# SparkX_EZ_LiPo_Power.net
KiCad netlist of a schematic drawn in EAGLE
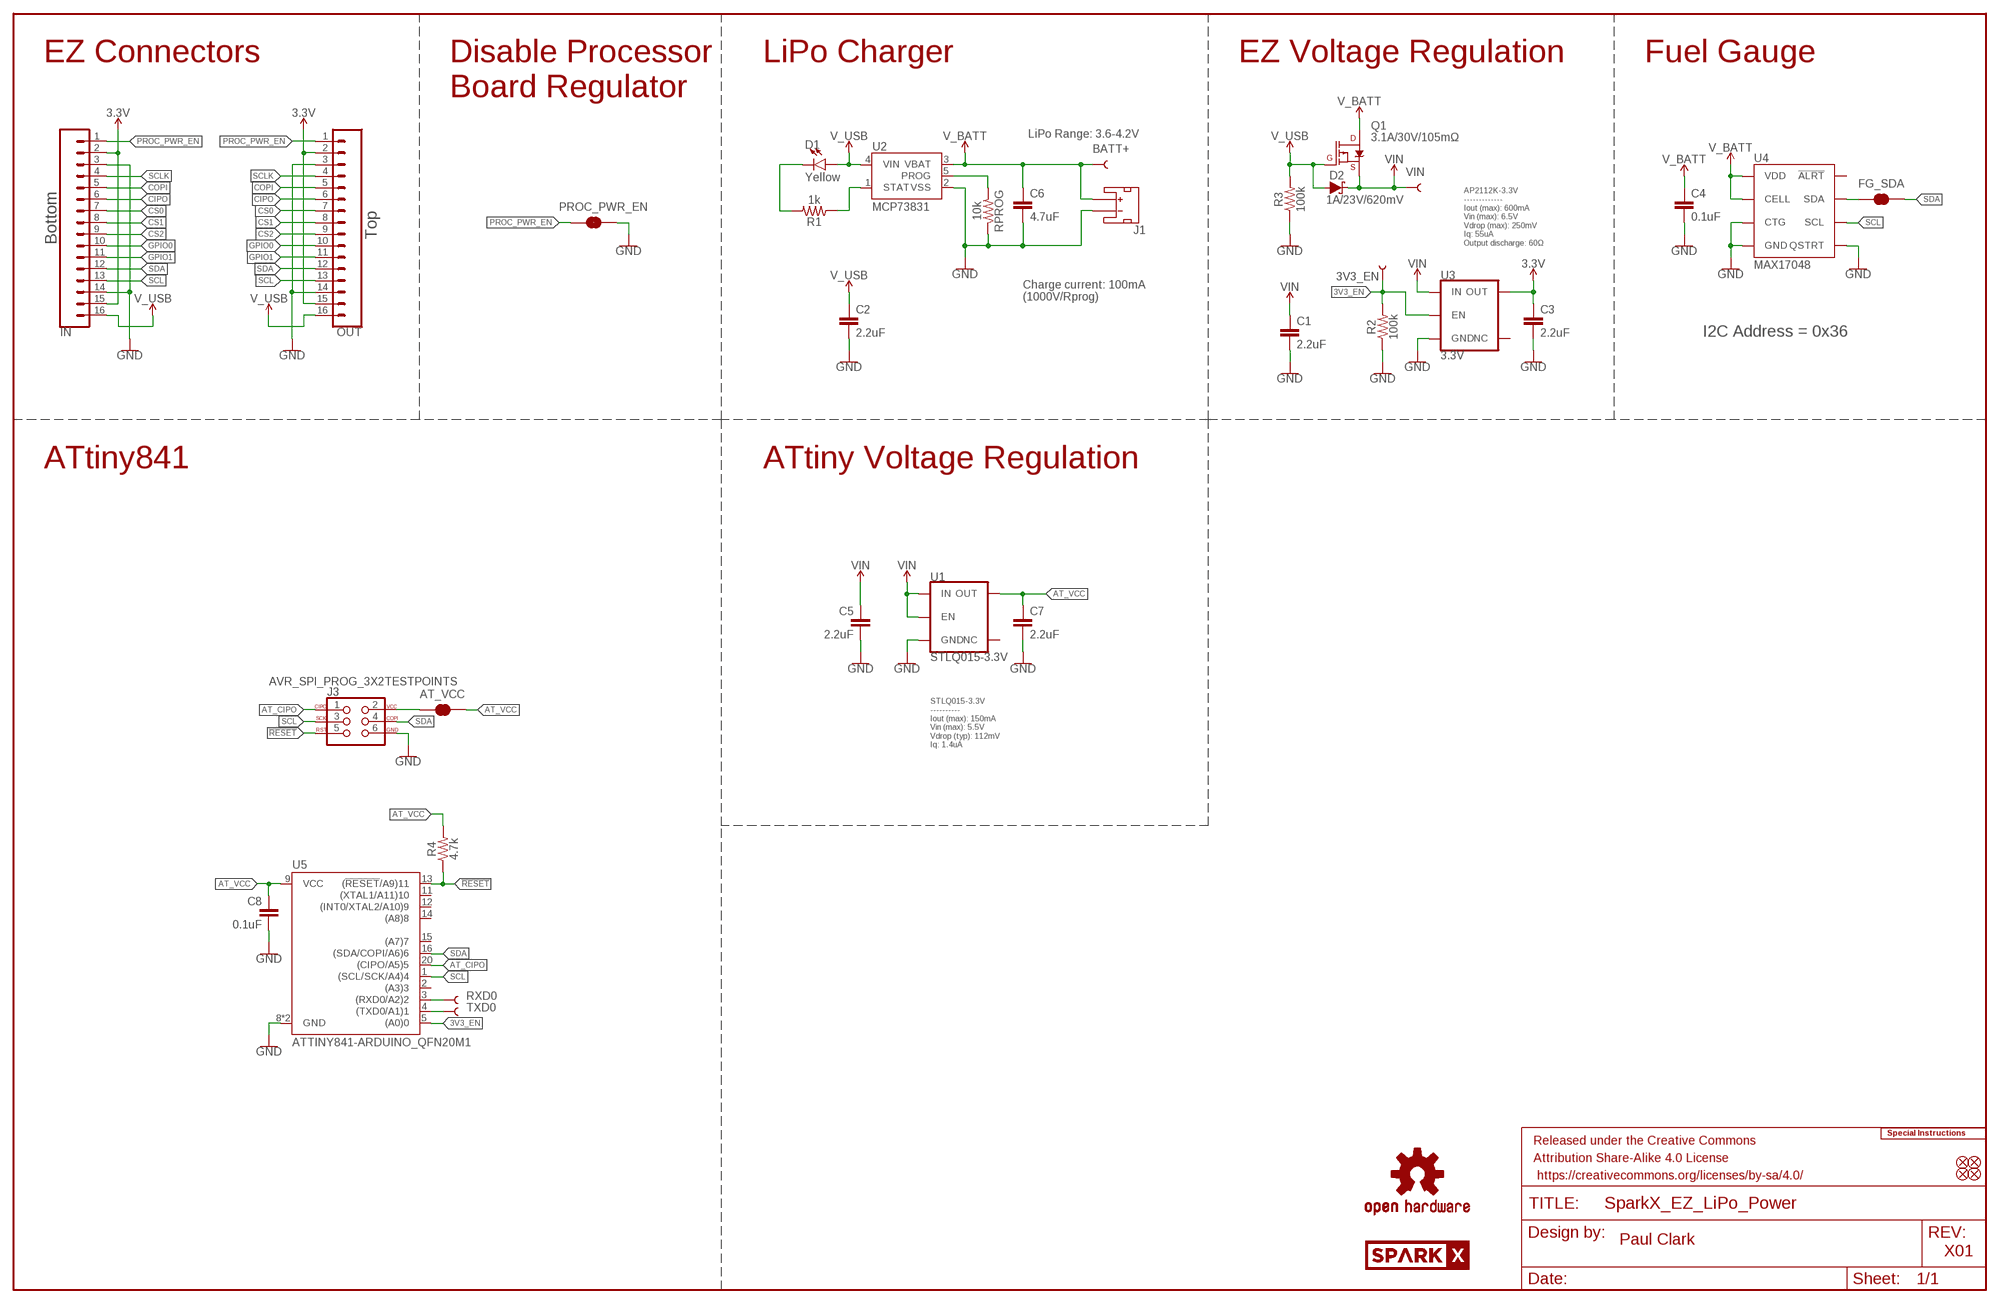
[diagram p0: schematic, sheet 1]

(export (version "E")
  (design (tool "Eeschema 10.0.6"))
  (components
    (comp (ref "3V3_EN")
      (value "TEST-POINT3X4")
      (footprint "eagle-import:PAD.03X.04")
      (libsource (lib "eagle-import") (part "TEST-POINT3X4"))
    )
    (comp (ref "AT_VCC")
      (value "JUMPER-SMT_2_NC_TRACE_SILK")
      (footprint "eagle-import:SMT-JUMPER_2_NC_TRACE_SILK")
      (libsource (lib "eagle-import") (part "JUMPER-SMT_2_NC_TRACE_SILK"))
    )
    (comp (ref "BATT+")
      (value "TEST-POINT3X4")
      (footprint "eagle-import:PAD.03X.04")
      (libsource (lib "eagle-import") (part "TEST-POINT3X4"))
    )
    (comp (ref "C1")
      (value "2.2uF")
      (footprint "eagle-import:0402-TIGHT")
      (libsource (lib "eagle-import") (part "2.2UF-0402_TIGHT-10V-10%-X5R"))
    )
    (comp (ref "C2")
      (value "2.2uF")
      (footprint "eagle-import:0402-TIGHT")
      (libsource (lib "eagle-import") (part "2.2UF-0402_TIGHT-10V-10%-X5R"))
    )
    (comp (ref "C3")
      (value "2.2uF")
      (footprint "eagle-import:0402-TIGHT")
      (libsource (lib "eagle-import") (part "2.2UF-0402_TIGHT-10V-10%-X5R"))
    )
    (comp (ref "C4")
      (value "0.1uF")
      (footprint "eagle-import:0402-TIGHT")
      (libsource (lib "eagle-import") (part "0.1UF-0402T-6.3V-10%-X7R"))
    )
    (comp (ref "C5")
      (value "2.2uF")
      (footprint "eagle-import:0402-TIGHT")
      (libsource (lib "eagle-import") (part "2.2UF-0402_TIGHT-10V-10%-X5R"))
    )
    (comp (ref "C6")
      (value "4.7uF")
      (footprint "eagle-import:0402-TIGHT")
      (libsource (lib "eagle-import") (part "4.7UF-0402_TIGHT-6.3V-20%-X5R"))
    )
    (comp (ref "C7")
      (value "2.2uF")
      (footprint "eagle-import:0402-TIGHT")
      (libsource (lib "eagle-import") (part "2.2UF-0402_TIGHT-10V-10%-X5R"))
    )
    (comp (ref "C8")
      (value "0.1uF")
      (footprint "eagle-import:0402-TIGHT")
      (libsource (lib "eagle-import") (part "0.1UF-0402T-6.3V-10%-X7R"))
    )
    (comp (ref "D1")
      (value "Yellow")
      (footprint "eagle-import:LED-0603")
      (libsource (lib "eagle-import") (part "LED-YELLOW0603"))
    )
    (comp (ref "D2")
      (value "1A/23V/620mV")
      (footprint "eagle-import:SOD-323")
      (libsource (lib "eagle-import") (part "DIODE-SCHOTTKY-BAT20J"))
    )
    (comp (ref "FD1")
      (value "FIDUCIALUFIDUCIAL")
      (footprint "eagle-import:FIDUCIAL-MICRO")
      (libsource (lib "eagle-import") (part "FIDUCIALUFIDUCIAL"))
    )
    (comp (ref "FD2")
      (value "FIDUCIALUFIDUCIAL")
      (footprint "eagle-import:FIDUCIAL-MICRO")
      (libsource (lib "eagle-import") (part "FIDUCIALUFIDUCIAL"))
    )
    (comp (ref "FD3")
      (value "FIDUCIALUFIDUCIAL")
      (footprint "eagle-import:FIDUCIAL-MICRO")
      (libsource (lib "eagle-import") (part "FIDUCIALUFIDUCIAL"))
    )
    (comp (ref "FD4")
      (value "FIDUCIALUFIDUCIAL")
      (footprint "eagle-import:FIDUCIAL-MICRO")
      (libsource (lib "eagle-import") (part "FIDUCIALUFIDUCIAL"))
    )
    (comp (ref "FG_SDA")
      (value "JUMPER-SMT_2_NC_TRACE_SILK")
      (footprint "eagle-import:SMT-JUMPER_2_NC_TRACE_SILK")
      (libsource (lib "eagle-import") (part "JUMPER-SMT_2_NC_TRACE_SILK"))
    )
    (comp (ref "FRAME1")
      (value "FRAME-LEDGER")
      (footprint "eagle-import:CREATIVE_COMMONS")
      (libsource (lib "eagle-import") (part "FRAME-LEDGER"))
    )
    (comp (ref "IN")
      (value "CONN_16FPC_16_0.5MM")
      (footprint "eagle-import:FPC_16_0.5MM")
      (libsource (lib "eagle-import") (part "CONN_16FPC_16_0.5MM"))
    )
    (comp (ref "J1")
      (value "JST_2MM_MALE")
      (footprint "eagle-import:JST-2-SMD")
      (libsource (lib "eagle-import") (part "JST_2MM_MALE"))
    )
    (comp (ref "J3")
      (value "AVR_SPI_PROG_3X2TESTPOINTS")
      (footprint "eagle-import:2X3_TEST_POINTS")
      (libsource (lib "eagle-import") (part "AVR_SPI_PROG_3X2TESTPOINTS"))
    )
    (comp (ref "LOGO1")
      (value "SPECIAL_INSTRUCTIONS-ORDERING")
      (footprint "eagle-import:ORDERING_INSTRUCTIONS")
      (libsource (lib "eagle-import") (part "SPECIAL_INSTRUCTIONS-ORDERING"))
    )
    (comp (ref "LOGO2")
      (value "OSHW-LOGOMINI")
      (footprint "eagle-import:OSHW-LOGO-MINI")
      (libsource (lib "eagle-import") (part "OSHW-LOGOMINI"))
    )
    (comp (ref "LOGO3")
      (value "OSHW-LOGOMINI")
      (footprint "eagle-import:OSHW-LOGO-MINI")
      (libsource (lib "eagle-import") (part "OSHW-LOGOMINI"))
    )
    (comp (ref "OUT")
      (value "CONN_16FPC_16_0.5MM")
      (footprint "eagle-import:FPC_16_0.5MM")
      (libsource (lib "eagle-import") (part "CONN_16FPC_16_0.5MM"))
    )
    (comp (ref "PROC_PWR_EN")
      (value "JUMPER-SMT_2_NC_TRACE_SILK")
      (footprint "eagle-import:SMT-JUMPER_2_NC_TRACE_SILK")
      (libsource (lib "eagle-import") (part "JUMPER-SMT_2_NC_TRACE_SILK"))
    )
    (comp (ref "Q1")
      (value "3.1A/30V/105mΩ")
      (footprint "eagle-import:SOT23-3")
      (libsource (lib "eagle-import") (part "MOSFET_PCH-DMG2307L"))
    )
    (comp (ref "R1")
      (value "1k")
      (footprint "eagle-import:0402-TIGHT")
      (libsource (lib "eagle-import") (part "1KOHM-0402T-1/16W-1%"))
    )
    (comp (ref "R2")
      (value "100k")
      (footprint "eagle-import:0402-TIGHT")
      (libsource (lib "eagle-import") (part "100KOHM-0402T-1/16W-1%"))
    )
    (comp (ref "R3")
      (value "100k")
      (footprint "eagle-import:0402-TIGHT")
      (libsource (lib "eagle-import") (part "100KOHM-0402T-1/16W-1%"))
    )
    (comp (ref "R4")
      (value "4.7k")
      (footprint "eagle-import:0402-TIGHT")
      (libsource (lib "eagle-import") (part "4.7KOHM-0402T-1/16W-1%"))
    )
    (comp (ref "RPROG")
      (value "10k")
      (footprint "eagle-import:0402-TIGHT")
      (libsource (lib "eagle-import") (part "10KOHM-0402T-1/16W-1%"))
    )
    (comp (ref "RXD0")
      (value "TEST-POINT3X4")
      (footprint "eagle-import:PAD.03X.04")
      (libsource (lib "eagle-import") (part "TEST-POINT3X4"))
    )
    (comp (ref "TXD0")
      (value "TEST-POINT3X4")
      (footprint "eagle-import:PAD.03X.04")
      (libsource (lib "eagle-import") (part "TEST-POINT3X4"))
    )
    (comp (ref "U$1")
      (value "SPARKX-LOGO3")
      (footprint "eagle-import:SPARKX-SMALL")
      (libsource (lib "eagle-import") (part "SPARKX-LOGO3"))
    )
    (comp (ref "U1")
      (value "STLQ015-3.3V")
      (footprint "eagle-import:SOT23-5")
      (libsource (lib "eagle-import") (part "STLQ015-3.3V"))
    )
    (comp (ref "U2")
      (value "MCP73831")
      (footprint "eagle-import:SOT23-5")
      (libsource (lib "eagle-import") (part "MCP73831"))
    )
    (comp (ref "U3")
      (value "3.3V")
      (footprint "eagle-import:SOT23-5")
      (libsource (lib "eagle-import") (part "V_REG_AP2112K-3.3V"))
    )
    (comp (ref "U4")
      (value "MAX17048")
      (footprint "eagle-import:DFN-8")
      (libsource (lib "eagle-import") (part "MAX17048DFN8"))
    )
    (comp (ref "U5")
      (value "ATTINY841-ARDUINO_QFN20M1")
      (footprint "eagle-import:QFN20_20M1")
      (fields (field (name "DIGIKEY_PART") "ATTINY841-MU-ND"))
      (libsource (lib "eagle-import") (part "ATTINY841-ARDUINO_QFN20M1"))
    )
    (comp (ref "VIN")
      (value "TEST-POINT3X4")
      (footprint "eagle-import:PAD.03X.04")
      (libsource (lib "eagle-import") (part "TEST-POINT3X4"))
    )
  )
  (nets
    (net (code "1") (name "/~{RESET}") (class "Default")
      (node (ref "J3") (pin "5") (pinfunction "5_5") (pintype "passive"))
      (node (ref "R4") (pin "1") (pinfunction "1_1") (pintype "passive"))
      (node (ref "U5") (pin "13") (pinfunction "(~{RESET}/A9)11_13") (pintype "bidirectional"))
    )
    (net (code "2") (name "3.3V") (class "Default")
      (node (ref "C3") (pin "1") (pinfunction "1_1") (pintype "passive"))
      (node (ref "IN") (pin "15") (pinfunction "15_15") (pintype "passive"))
      (node (ref "IN") (pin "2") (pinfunction "2_2") (pintype "passive"))
      (node (ref "OUT") (pin "15") (pinfunction "15_15") (pintype "passive"))
      (node (ref "OUT") (pin "2") (pinfunction "2_2") (pintype "passive"))
      (node (ref "U3") (pin "5") (pinfunction "OUT_5") (pintype "passive"))
    )
    (net (code "3") (name "3V3_EN") (class "Default")
      (node (ref "3V3_EN") (pin "1") (pinfunction "1_1") (pintype "bidirectional"))
      (node (ref "R2") (pin "2") (pinfunction "2_2") (pintype "passive"))
      (node (ref "U3") (pin "3") (pinfunction "EN_3") (pintype "input"))
      (node (ref "U5") (pin "5") (pinfunction "(A0)0_5") (pintype "bidirectional"))
    )
    (net (code "4") (name "AT_CIPO") (class "Default")
      (node (ref "J3") (pin "1") (pinfunction "1_1") (pintype "passive"))
      (node (ref "U5") (pin "20") (pinfunction "(CIPO/A5)5_20") (pintype "bidirectional"))
    )
    (net (code "5") (name "AT_VCC") (class "Default")
      (node (ref "AT_VCC") (pin "2") (pinfunction "2_2") (pintype "passive"))
      (node (ref "C7") (pin "1") (pinfunction "1_1") (pintype "passive"))
      (node (ref "C8") (pin "1") (pinfunction "1_1") (pintype "passive"))
      (node (ref "R4") (pin "2") (pinfunction "2_2") (pintype "passive"))
      (node (ref "U1") (pin "5") (pinfunction "OUT_5") (pintype "passive"))
      (node (ref "U5") (pin "9") (pinfunction "VCC_9") (pintype "power_in"))
    )
    (net (code "6") (name "CIPO") (class "Default")
      (node (ref "IN") (pin "6") (pinfunction "6_6") (pintype "passive"))
      (node (ref "OUT") (pin "6") (pinfunction "6_6") (pintype "passive"))
    )
    (net (code "7") (name "COPI") (class "Default")
      (node (ref "IN") (pin "5") (pinfunction "5_5") (pintype "passive"))
      (node (ref "OUT") (pin "5") (pinfunction "5_5") (pintype "passive"))
    )
    (net (code "8") (name "CS0") (class "Default")
      (node (ref "IN") (pin "7") (pinfunction "7_7") (pintype "passive"))
      (node (ref "OUT") (pin "7") (pinfunction "7_7") (pintype "passive"))
    )
    (net (code "9") (name "CS1") (class "Default")
      (node (ref "IN") (pin "8") (pinfunction "8_8") (pintype "passive"))
      (node (ref "OUT") (pin "8") (pinfunction "8_8") (pintype "passive"))
    )
    (net (code "10") (name "CS2") (class "Default")
      (node (ref "IN") (pin "9") (pinfunction "9_9") (pintype "passive"))
      (node (ref "OUT") (pin "9") (pinfunction "9_9") (pintype "passive"))
    )
    (net (code "11") (name "GND") (class "Default")
      (node (ref "C1") (pin "2") (pinfunction "2_2") (pintype "passive"))
      (node (ref "C2") (pin "2") (pinfunction "2_2") (pintype "passive"))
      (node (ref "C3") (pin "2") (pinfunction "2_2") (pintype "passive"))
      (node (ref "C4") (pin "2") (pinfunction "2_2") (pintype "passive"))
      (node (ref "C5") (pin "2") (pinfunction "2_2") (pintype "passive"))
      (node (ref "C6") (pin "2") (pinfunction "2_2") (pintype "passive"))
      (node (ref "C7") (pin "2") (pinfunction "2_2") (pintype "passive"))
      (node (ref "C8") (pin "2") (pinfunction "2_2") (pintype "passive"))
      (node (ref "IN") (pin "14") (pinfunction "14_14") (pintype "passive"))
      (node (ref "IN") (pin "3") (pinfunction "3_3") (pintype "passive"))
      (node (ref "J1") (pin "1") (pinfunction "-_1") (pintype "bidirectional"))
      (node (ref "J3") (pin "6") (pinfunction "6_6") (pintype "passive"))
      (node (ref "OUT") (pin "14") (pinfunction "14_14") (pintype "passive"))
      (node (ref "OUT") (pin "3") (pinfunction "3_3") (pintype "passive"))
      (node (ref "PROC_PWR_EN") (pin "2") (pinfunction "2_2") (pintype "passive"))
      (node (ref "R2") (pin "1") (pinfunction "1_1") (pintype "passive"))
      (node (ref "R3") (pin "1") (pinfunction "1_1") (pintype "passive"))
      (node (ref "RPROG") (pin "1") (pinfunction "1_1") (pintype "passive"))
      (node (ref "U1") (pin "2") (pinfunction "GND_2") (pintype "input"))
      (node (ref "U2") (pin "2") (pinfunction "VSS_2") (pintype "power_in"))
      (node (ref "U3") (pin "2") (pinfunction "GND_2") (pintype "input"))
      (node (ref "U4") (pin "1") (pinfunction "CTG_1") (pintype "input"))
      (node (ref "U4") (pin "4") (pinfunction "GND_4") (pintype "bidirectional"))
      (node (ref "U4") (pin "6") (pinfunction "QSTRT_6") (pintype "bidirectional"))
      (node (ref "U4") (pin "9") (pinfunction "GND_9") (pintype "bidirectional"))
      (node (ref "U5") (pin "8") (pinfunction "GND_8") (pintype "power_in"))
      (node (ref "U5") (pin "PAD") (pinfunction "GND_PAD") (pintype "power_in"))
    )
    (net (code "12") (name "GPIO0") (class "Default")
      (node (ref "IN") (pin "10") (pinfunction "10_10") (pintype "passive"))
      (node (ref "OUT") (pin "10") (pinfunction "10_10") (pintype "passive"))
    )
    (net (code "13") (name "GPIO1") (class "Default")
      (node (ref "IN") (pin "11") (pinfunction "11_11") (pintype "passive"))
      (node (ref "OUT") (pin "11") (pinfunction "11_11") (pintype "passive"))
    )
    (net (code "14") (name "Net-(AT_VCC-Pad1)") (class "Default")
      (node (ref "AT_VCC") (pin "1") (pinfunction "1_1") (pintype "passive"))
      (node (ref "J3") (pin "2") (pinfunction "2_2") (pintype "passive"))
    )
    (net (code "15") (name "Net-(D1-PadC)") (class "Default")
      (node (ref "D1") (pin "C") (pinfunction "C_C") (pintype "passive"))
      (node (ref "R1") (pin "2") (pinfunction "2_2") (pintype "passive"))
    )
    (net (code "16") (name "Net-(U2-PROG)") (class "Default")
      (node (ref "RPROG") (pin "2") (pinfunction "2_2") (pintype "passive"))
      (node (ref "U2") (pin "5") (pinfunction "PROG_5") (pintype "input"))
    )
    (net (code "17") (name "Net-(U2-STAT)") (class "Default")
      (node (ref "R1") (pin "1") (pinfunction "1_1") (pintype "passive"))
      (node (ref "U2") (pin "1") (pinfunction "STAT_1") (pintype "output"))
    )
    (net (code "18") (name "Net-(U4-SDA)") (class "Default")
      (node (ref "FG_SDA") (pin "1") (pinfunction "1_1") (pintype "passive"))
      (node (ref "U4") (pin "8") (pinfunction "SDA_8") (pintype "input"))
    )
    (net (code "19") (name "Net-(U5-(RXD0{slash}A2)2)") (class "Default")
      (node (ref "RXD0") (pin "1") (pinfunction "1_1") (pintype "bidirectional"))
      (node (ref "U5") (pin "3") (pinfunction "(RXD0/A2)2_3") (pintype "bidirectional"))
    )
    (net (code "20") (name "Net-(U5-(TXD0{slash}A1)1)") (class "Default")
      (node (ref "TXD0") (pin "1") (pinfunction "1_1") (pintype "bidirectional"))
      (node (ref "U5") (pin "4") (pinfunction "(TXD0/A1)1_4") (pintype "bidirectional"))
    )
    (net (code "21") (name "PROC_PWR_EN") (class "Default")
      (node (ref "IN") (pin "1") (pinfunction "1_1") (pintype "passive"))
      (node (ref "OUT") (pin "1") (pinfunction "1_1") (pintype "passive"))
      (node (ref "PROC_PWR_EN") (pin "1") (pinfunction "1_1") (pintype "passive"))
    )
    (net (code "22") (name "SCL") (class "Default")
      (node (ref "IN") (pin "13") (pinfunction "13_13") (pintype "passive"))
      (node (ref "J3") (pin "3") (pinfunction "3_3") (pintype "passive"))
      (node (ref "OUT") (pin "13") (pinfunction "13_13") (pintype "passive"))
      (node (ref "U4") (pin "7") (pinfunction "SCL_7") (pintype "output"))
      (node (ref "U5") (pin "1") (pinfunction "(SCL/SCK/A4)4_1") (pintype "bidirectional"))
    )
    (net (code "23") (name "SCLK") (class "Default")
      (node (ref "IN") (pin "4") (pinfunction "4_4") (pintype "passive"))
      (node (ref "OUT") (pin "4") (pinfunction "4_4") (pintype "passive"))
    )
    (net (code "24") (name "SDA") (class "Default")
      (node (ref "FG_SDA") (pin "2") (pinfunction "2_2") (pintype "passive"))
      (node (ref "IN") (pin "12") (pinfunction "12_12") (pintype "passive"))
      (node (ref "J3") (pin "4") (pinfunction "4_4") (pintype "passive"))
      (node (ref "OUT") (pin "12") (pinfunction "12_12") (pintype "passive"))
      (node (ref "U5") (pin "16") (pinfunction "(SDA/COPI/A6)6_16") (pintype "bidirectional"))
    )
    (net (code "25") (name "VIN") (class "Default")
      (node (ref "C1") (pin "1") (pinfunction "1_1") (pintype "passive"))
      (node (ref "C5") (pin "1") (pinfunction "1_1") (pintype "passive"))
      (node (ref "D2") (pin "C") (pinfunction "C_C") (pintype "passive"))
      (node (ref "Q1") (pin "2") (pinfunction "S_2") (pintype "bidirectional"))
      (node (ref "U1") (pin "1") (pinfunction "IN_1") (pintype "input"))
      (node (ref "U1") (pin "3") (pinfunction "EN_3") (pintype "input"))
      (node (ref "U3") (pin "1") (pinfunction "IN_1") (pintype "input"))
      (node (ref "VIN") (pin "1") (pinfunction "1_1") (pintype "bidirectional"))
    )
    (net (code "26") (name "V_BATT") (class "Default")
      (node (ref "BATT+") (pin "1") (pinfunction "1_1") (pintype "bidirectional"))
      (node (ref "C4") (pin "1") (pinfunction "1_1") (pintype "passive"))
      (node (ref "C6") (pin "1") (pinfunction "1_1") (pintype "passive"))
      (node (ref "J1") (pin "2") (pinfunction "+_2") (pintype "bidirectional"))
      (node (ref "Q1") (pin "3") (pinfunction "D_3") (pintype "bidirectional"))
      (node (ref "U2") (pin "3") (pinfunction "VBAT_3") (pintype "power_in"))
      (node (ref "U4") (pin "2") (pinfunction "CELL_2") (pintype "input"))
      (node (ref "U4") (pin "3") (pinfunction "VDD_3") (pintype "bidirectional"))
    )
    (net (code "27") (name "V_USB") (class "Default")
      (node (ref "C2") (pin "1") (pinfunction "1_1") (pintype "passive"))
      (node (ref "D1") (pin "A") (pinfunction "A_A") (pintype "passive"))
      (node (ref "D2") (pin "A") (pinfunction "A_A") (pintype "passive"))
      (node (ref "IN") (pin "16") (pinfunction "16_16") (pintype "passive"))
      (node (ref "OUT") (pin "16") (pinfunction "16_16") (pintype "passive"))
      (node (ref "Q1") (pin "1") (pinfunction "G_1") (pintype "bidirectional"))
      (node (ref "R3") (pin "2") (pinfunction "2_2") (pintype "passive"))
      (node (ref "U2") (pin "4") (pinfunction "VIN_4") (pintype "power_in"))
    )
    (net (code "28") (name "unconnected-(J1-PAD1-PadNC1)") (class "Default")
      (node (ref "J1") (pin "NC1") (pinfunction "PAD1_NC1") (pintype "bidirectional"))
    )
    (net (code "29") (name "unconnected-(J1-PAD2-PadNC2)") (class "Default")
      (node (ref "J1") (pin "NC2") (pinfunction "PAD2_NC2") (pintype "bidirectional"))
    )
    (net (code "30") (name "unconnected-(U1-NC-Pad4)") (class "Default")
      (node (ref "U1") (pin "4") (pinfunction "NC_4") (pintype "no_connect"))
    )
    (net (code "31") (name "unconnected-(U3-NC-Pad4)") (class "Default")
      (node (ref "U3") (pin "4") (pinfunction "NC_4") (pintype "no_connect"))
    )
    (net (code "32") (name "unconnected-(U4-~{ALRT}-Pad5)") (class "Default")
      (node (ref "U4") (pin "5") (pinfunction "~{ALRT}_5") (pintype "bidirectional"))
    )
    (net (code "33") (name "unconnected-(U5-(A3)3-Pad2)") (class "Default")
      (node (ref "U5") (pin "2") (pinfunction "(A3)3_2") (pintype "bidirectional"))
    )
    (net (code "34") (name "unconnected-(U5-(A7)7-Pad15)") (class "Default")
      (node (ref "U5") (pin "15") (pinfunction "(A7)7_15") (pintype "bidirectional"))
    )
    (net (code "35") (name "unconnected-(U5-(A8)8-Pad14)") (class "Default")
      (node (ref "U5") (pin "14") (pinfunction "(A8)8_14") (pintype "bidirectional"))
    )
    (net (code "36") (name "unconnected-(U5-(INT0{slash}XTAL2{slash}A10)9-Pad12)") (class "Default")
      (node (ref "U5") (pin "12") (pinfunction "(INT0/XTAL2/A10)9_12") (pintype "bidirectional"))
    )
    (net (code "37") (name "unconnected-(U5-(XTAL1{slash}A11)10-Pad11)") (class "Default")
      (node (ref "U5") (pin "11") (pinfunction "(XTAL1/A11)10_11") (pintype "bidirectional"))
    )
  )
)
